# main_v2_0.net
KiCad netlist of a schematic drawn in EAGLE
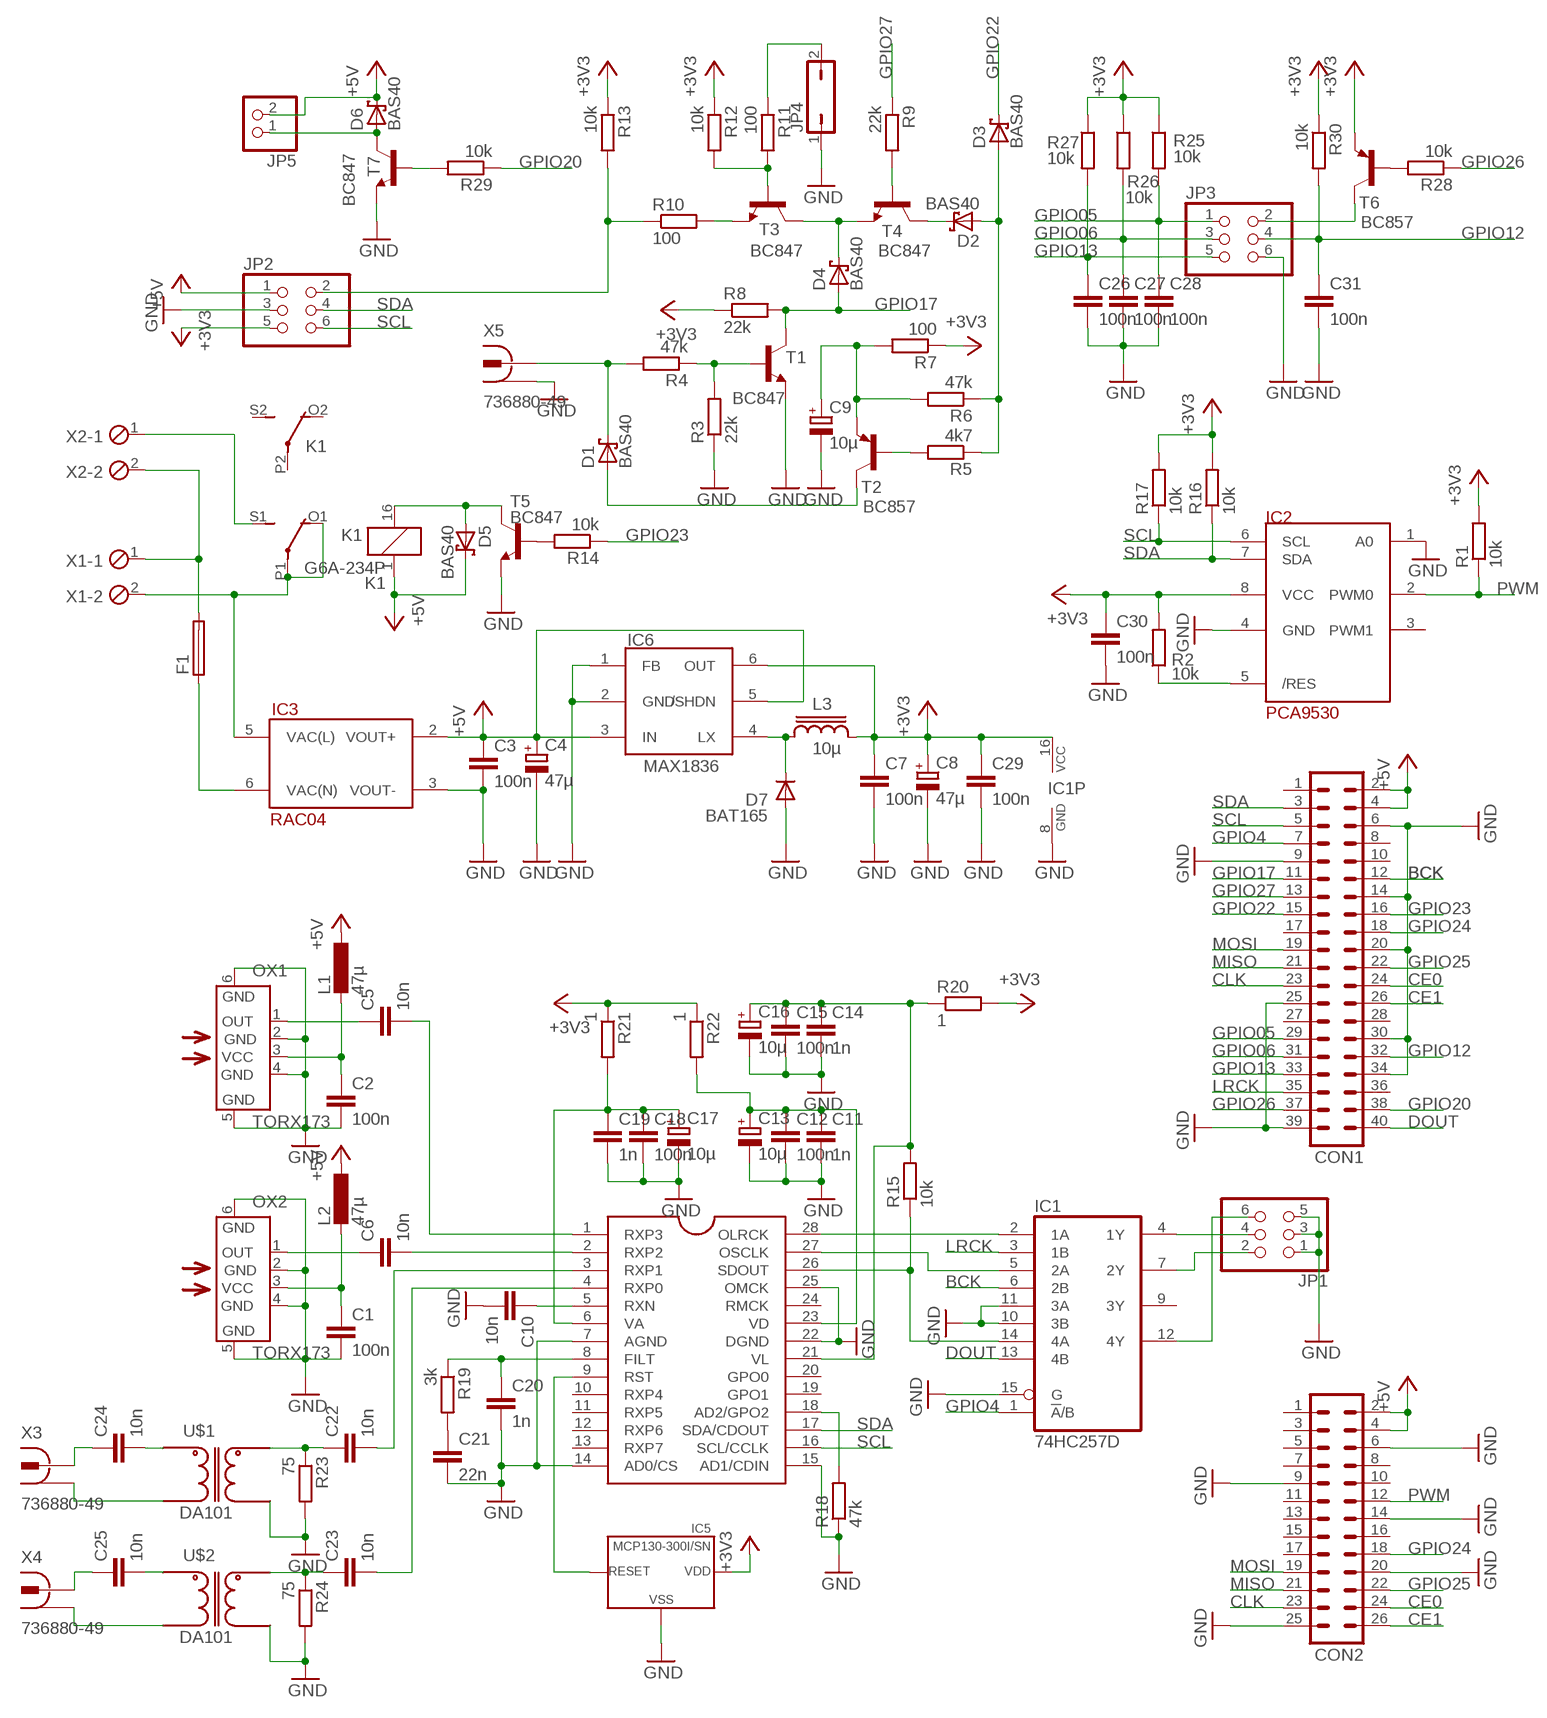
[diagram p0: schematic, sheet 1]

(export (version "E")
  (design (tool "Eeschema 10.0.6"))
  (components
    (comp (ref "C1")
      (value "100n")
      (footprint "eagle-import:C0805")
      (libsource (lib "eagle-import") (part "C-EUC0805"))
    )
    (comp (ref "C2")
      (value "100n")
      (footprint "eagle-import:C0805")
      (libsource (lib "eagle-import") (part "C-EUC0805"))
    )
    (comp (ref "C3")
      (value "100n")
      (footprint "eagle-import:C0805")
      (libsource (lib "eagle-import") (part "C-EUC0805"))
    )
    (comp (ref "C4")
      (value "47µ")
      (footprint "eagle-import:CT3528")
      (libsource (lib "eagle-import") (part "CPOL-EUCT3528"))
    )
    (comp (ref "C5")
      (value "10n")
      (footprint "eagle-import:C0805")
      (libsource (lib "eagle-import") (part "C-EUC0805"))
    )
    (comp (ref "C6")
      (value "10n")
      (footprint "eagle-import:C0805")
      (libsource (lib "eagle-import") (part "C-EUC0805"))
    )
    (comp (ref "C7")
      (value "100n")
      (footprint "eagle-import:C0805")
      (libsource (lib "eagle-import") (part "C-EUC0805"))
    )
    (comp (ref "C8")
      (value "47µ")
      (footprint "eagle-import:CT3528")
      (libsource (lib "eagle-import") (part "CPOL-EUCT3528"))
    )
    (comp (ref "C9")
      (value "10µ")
      (footprint "eagle-import:CT3216")
      (libsource (lib "eagle-import") (part "CPOL-EUCT3216"))
    )
    (comp (ref "C10")
      (value "10n")
      (footprint "eagle-import:C0805")
      (libsource (lib "eagle-import") (part "C-EUC0805"))
    )
    (comp (ref "C11")
      (value "1n")
      (footprint "eagle-import:C0805")
      (libsource (lib "eagle-import") (part "C-EUC0805"))
    )
    (comp (ref "C12")
      (value "100n")
      (footprint "eagle-import:C0805")
      (libsource (lib "eagle-import") (part "C-EUC0805"))
    )
    (comp (ref "C13")
      (value "10µ")
      (footprint "eagle-import:CT3216")
      (libsource (lib "eagle-import") (part "CPOL-EUCT3216"))
    )
    (comp (ref "C14")
      (value "1n")
      (footprint "eagle-import:C0805")
      (libsource (lib "eagle-import") (part "C-EUC0805"))
    )
    (comp (ref "C15")
      (value "100n")
      (footprint "eagle-import:C0805")
      (libsource (lib "eagle-import") (part "C-EUC0805"))
    )
    (comp (ref "C16")
      (value "10µ")
      (footprint "eagle-import:CT3216")
      (libsource (lib "eagle-import") (part "CPOL-EUCT3216"))
    )
    (comp (ref "C17")
      (value "10µ")
      (footprint "eagle-import:CT3216")
      (libsource (lib "eagle-import") (part "CPOL-EUCT3216"))
    )
    (comp (ref "C18")
      (value "100n")
      (footprint "eagle-import:C0805")
      (libsource (lib "eagle-import") (part "C-EUC0805"))
    )
    (comp (ref "C19")
      (value "1n")
      (footprint "eagle-import:C0805")
      (libsource (lib "eagle-import") (part "C-EUC0805"))
    )
    (comp (ref "C20")
      (value "1n")
      (footprint "eagle-import:C0805")
      (libsource (lib "eagle-import") (part "C-EUC0805"))
    )
    (comp (ref "C21")
      (value "22n")
      (footprint "eagle-import:C0805")
      (libsource (lib "eagle-import") (part "C-EUC0805"))
    )
    (comp (ref "C22")
      (value "10n")
      (footprint "eagle-import:C0805")
      (libsource (lib "eagle-import") (part "C-EUC0805"))
    )
    (comp (ref "C23")
      (value "10n")
      (footprint "eagle-import:C0805")
      (libsource (lib "eagle-import") (part "C-EUC0805"))
    )
    (comp (ref "C24")
      (value "10n")
      (footprint "eagle-import:C0805")
      (libsource (lib "eagle-import") (part "C-EUC0805"))
    )
    (comp (ref "C25")
      (value "10n")
      (footprint "eagle-import:C0805")
      (libsource (lib "eagle-import") (part "C-EUC0805"))
    )
    (comp (ref "C26")
      (value "100n")
      (footprint "eagle-import:C0805")
      (libsource (lib "eagle-import") (part "C-EUC0805"))
    )
    (comp (ref "C27")
      (value "100n")
      (footprint "eagle-import:C0805")
      (libsource (lib "eagle-import") (part "C-EUC0805"))
    )
    (comp (ref "C28")
      (value "100n")
      (footprint "eagle-import:C0805")
      (libsource (lib "eagle-import") (part "C-EUC0805"))
    )
    (comp (ref "C29")
      (value "100n")
      (footprint "eagle-import:C0805")
      (libsource (lib "eagle-import") (part "C-EUC0805"))
    )
    (comp (ref "C30")
      (value "100n")
      (footprint "eagle-import:C0805")
      (libsource (lib "eagle-import") (part "C-EUC0805"))
    )
    (comp (ref "C31")
      (value "100n")
      (footprint "eagle-import:C0805")
      (libsource (lib "eagle-import") (part "C-EUC0805"))
    )
    (comp (ref "CON1")
      (value "MA20-2")
      (footprint "eagle-import:MA20-2")
      (libsource (lib "eagle-import") (part "MA20-2"))
    )
    (comp (ref "CON2")
      (value "MA13-2")
      (footprint "eagle-import:MA13-2")
      (libsource (lib "eagle-import") (part "MA13-2"))
    )
    (comp (ref "D1")
      (value "BAS40")
      (footprint "eagle-import:SOT23")
      (libsource (lib "eagle-import") (part "BAS40"))
    )
    (comp (ref "D2")
      (value "BAS40")
      (footprint "eagle-import:SOT23")
      (libsource (lib "eagle-import") (part "BAS40"))
    )
    (comp (ref "D3")
      (value "BAS40")
      (footprint "eagle-import:SOT23")
      (libsource (lib "eagle-import") (part "BAS40"))
    )
    (comp (ref "D4")
      (value "BAS40")
      (footprint "eagle-import:SOT23")
      (libsource (lib "eagle-import") (part "BAS40"))
    )
    (comp (ref "D5")
      (value "BAS40")
      (footprint "eagle-import:SOT23")
      (libsource (lib "eagle-import") (part "BAS40"))
    )
    (comp (ref "D6")
      (value "BAS40")
      (footprint "eagle-import:SOT23")
      (libsource (lib "eagle-import") (part "BAS40"))
    )
    (comp (ref "D7")
      (value "BAT165")
      (footprint "eagle-import:SOD-323F")
      (libsource (lib "eagle-import") (part "DIODE-SOD-323"))
    )
    (comp (ref "F1")
      (value "19560")
      (footprint "eagle-import:19560")
      (fields (field (name "MPN") "56000001009"))
      (libsource (lib "eagle-import") (part "19560"))
    )
    (comp (ref "IC1")
      (value "74HC257D")
      (footprint "eagle-import:SO16")
      (libsource (lib "eagle-import") (part "74257DHC"))
    )
    (comp (ref "IC2")
      (value "PCA9530")
      (footprint "eagle-import:SOIC-8")
      (libsource (lib "eagle-import") (part "PCA9530"))
    )
    (comp (ref "IC3")
      (value "RAC04")
      (footprint "eagle-import:RECOM-RAC04")
      (libsource (lib "eagle-import") (part "RAC04"))
    )
    (comp (ref "IC4")
      (value "CS8416")
      (footprint "eagle-import:SO28L")
      (libsource (lib "eagle-import") (part "CS8416-SOFTWAREMODESOFTWAREMODE"))
    )
    (comp (ref "IC5")
      (value "MCP130-300I/SN")
      (footprint "eagle-import:SOT-23")
      (libsource (lib "eagle-import") (part "MCP130/SN-300I"))
    )
    (comp (ref "IC6")
      (value "MAX1836")
      (footprint "eagle-import:SOT23-6L")
      (libsource (lib "eagle-import") (part "MAX1836SOT23"))
    )
    (comp (ref "JP1")
      (value "PINHD-2X3")
      (footprint "eagle-import:2X03")
      (libsource (lib "eagle-import") (part "PINHD-2X3"))
    )
    (comp (ref "JP2")
      (value "PINHD-2X3")
      (footprint "eagle-import:2X03")
      (libsource (lib "eagle-import") (part "PINHD-2X3"))
    )
    (comp (ref "JP3")
      (value "PINHD-2X3")
      (footprint "eagle-import:2X03")
      (libsource (lib "eagle-import") (part "PINHD-2X3"))
    )
    (comp (ref "JP4")
      (value "JP1Q")
      (footprint "eagle-import:JP1")
      (libsource (lib "eagle-import") (part "JP1Q"))
    )
    (comp (ref "JP5")
      (value "PINHD-1X2")
      (footprint "eagle-import:1X02")
      (libsource (lib "eagle-import") (part "PINHD-1X2"))
    )
    (comp (ref "K1")
      (value "G6A-234P")
      (footprint "eagle-import:G6A-234P")
      (libsource (lib "eagle-import") (part "G6A-234P"))
    )
    (comp (ref "L1")
      (value "47µ")
      (footprint "eagle-import:C1210")
      (libsource (lib "eagle-import") (part "L-EU"))
    )
    (comp (ref "L2")
      (value "47µ")
      (footprint "eagle-import:C1210")
      (libsource (lib "eagle-import") (part "L-EU"))
    )
    (comp (ref "L3")
      (value "10µ")
      (footprint "eagle-import:LPS4018")
      (libsource (lib "eagle-import") (part "LPS4018"))
    )
    (comp (ref "OX1")
      (value "TORX173")
      (footprint "eagle-import:TORX173")
      (libsource (lib "eagle-import") (part "TORX173"))
    )
    (comp (ref "OX2")
      (value "TORX173")
      (footprint "eagle-import:TORX173")
      (libsource (lib "eagle-import") (part "TORX173"))
    )
    (comp (ref "R1")
      (value "10k")
      (footprint "eagle-import:R0805")
      (libsource (lib "eagle-import") (part "R-EU_R0805"))
    )
    (comp (ref "R2")
      (value "10k")
      (footprint "eagle-import:R0805")
      (libsource (lib "eagle-import") (part "R-EU_R0805"))
    )
    (comp (ref "R3")
      (value "22k")
      (footprint "eagle-import:R0805")
      (libsource (lib "eagle-import") (part "R-EU_R0805"))
    )
    (comp (ref "R4")
      (value "47k")
      (footprint "eagle-import:R0805")
      (libsource (lib "eagle-import") (part "R-EU_R0805"))
    )
    (comp (ref "R5")
      (value "4k7")
      (footprint "eagle-import:R0805")
      (libsource (lib "eagle-import") (part "R-EU_R0805"))
    )
    (comp (ref "R6")
      (value "47k")
      (footprint "eagle-import:R0805")
      (libsource (lib "eagle-import") (part "R-EU_R0805"))
    )
    (comp (ref "R7")
      (value "100")
      (footprint "eagle-import:R0805")
      (libsource (lib "eagle-import") (part "R-EU_R0805"))
    )
    (comp (ref "R8")
      (value "22k")
      (footprint "eagle-import:R0805")
      (libsource (lib "eagle-import") (part "R-EU_R0805"))
    )
    (comp (ref "R9")
      (value "22k")
      (footprint "eagle-import:R0805")
      (libsource (lib "eagle-import") (part "R-EU_R0805"))
    )
    (comp (ref "R10")
      (value "100")
      (footprint "eagle-import:R0805")
      (libsource (lib "eagle-import") (part "R-EU_R0805"))
    )
    (comp (ref "R11")
      (value "100")
      (footprint "eagle-import:R0805")
      (libsource (lib "eagle-import") (part "R-EU_R0805"))
    )
    (comp (ref "R12")
      (value "10k")
      (footprint "eagle-import:R0805")
      (libsource (lib "eagle-import") (part "R-EU_R0805"))
    )
    (comp (ref "R13")
      (value "10k")
      (footprint "eagle-import:R0805")
      (libsource (lib "eagle-import") (part "R-EU_R0805"))
    )
    (comp (ref "R14")
      (value "10k")
      (footprint "eagle-import:R0805")
      (libsource (lib "eagle-import") (part "R-EU_R0805"))
    )
    (comp (ref "R15")
      (value "10k")
      (footprint "eagle-import:R0805")
      (libsource (lib "eagle-import") (part "R-EU_R0805"))
    )
    (comp (ref "R16")
      (value "10k")
      (footprint "eagle-import:R0805")
      (libsource (lib "eagle-import") (part "R-EU_R0805"))
    )
    (comp (ref "R17")
      (value "10k")
      (footprint "eagle-import:R0805")
      (libsource (lib "eagle-import") (part "R-EU_R0805"))
    )
    (comp (ref "R18")
      (value "47k")
      (footprint "eagle-import:R0805")
      (libsource (lib "eagle-import") (part "R-EU_R0805"))
    )
    (comp (ref "R19")
      (value "3k")
      (footprint "eagle-import:R0805")
      (libsource (lib "eagle-import") (part "R-EU_R0805"))
    )
    (comp (ref "R20")
      (value "1")
      (footprint "eagle-import:R0805")
      (libsource (lib "eagle-import") (part "R-EU_R0805"))
    )
    (comp (ref "R21")
      (value "1")
      (footprint "eagle-import:R0805")
      (libsource (lib "eagle-import") (part "R-EU_R0805"))
    )
    (comp (ref "R22")
      (value "1")
      (footprint "eagle-import:R0805")
      (libsource (lib "eagle-import") (part "R-EU_R0805"))
    )
    (comp (ref "R23")
      (value "75")
      (footprint "eagle-import:R0805")
      (libsource (lib "eagle-import") (part "R-EU_R0805"))
    )
    (comp (ref "R24")
      (value "75")
      (footprint "eagle-import:R0805")
      (libsource (lib "eagle-import") (part "R-EU_R0805"))
    )
    (comp (ref "R25")
      (value "10k")
      (footprint "eagle-import:R0805")
      (libsource (lib "eagle-import") (part "R-EU_R0805"))
    )
    (comp (ref "R26")
      (value "10k")
      (footprint "eagle-import:R0805")
      (libsource (lib "eagle-import") (part "R-EU_R0805"))
    )
    (comp (ref "R27")
      (value "10k")
      (footprint "eagle-import:R0805")
      (libsource (lib "eagle-import") (part "R-EU_R0805"))
    )
    (comp (ref "R28")
      (value "10k")
      (footprint "eagle-import:R0805")
      (libsource (lib "eagle-import") (part "R-EU_R0805"))
    )
    (comp (ref "R29")
      (value "10k")
      (footprint "eagle-import:R0805")
      (libsource (lib "eagle-import") (part "R-EU_R0805"))
    )
    (comp (ref "R30")
      (value "10k")
      (footprint "eagle-import:R0805")
      (libsource (lib "eagle-import") (part "R-EU_R0805"))
    )
    (comp (ref "T1")
      (value "BC847")
      (footprint "eagle-import:SOT23-BEC")
      (libsource (lib "eagle-import") (part "-NPN-SOT23-BECBC847"))
    )
    (comp (ref "T2")
      (value "BC857")
      (footprint "eagle-import:SOT23-BEC")
      (libsource (lib "eagle-import") (part "-PNP-SOT23-BECBC857A"))
    )
    (comp (ref "T3")
      (value "BC847")
      (footprint "eagle-import:SOT23-BEC")
      (libsource (lib "eagle-import") (part "-NPN-SOT23-BECBC847"))
    )
    (comp (ref "T4")
      (value "BC847")
      (footprint "eagle-import:SOT23-BEC")
      (libsource (lib "eagle-import") (part "-NPN-SOT23-BECBC847"))
    )
    (comp (ref "T5")
      (value "BC847")
      (footprint "eagle-import:SOT23-BEC")
      (libsource (lib "eagle-import") (part "-NPN-SOT23-BECBC847"))
    )
    (comp (ref "T6")
      (value "BC857")
      (footprint "eagle-import:SOT23-BEC")
      (libsource (lib "eagle-import") (part "-PNP-SOT23-BECBC857A"))
    )
    (comp (ref "T7")
      (value "BC847")
      (footprint "eagle-import:SOT23-BEC")
      (libsource (lib "eagle-import") (part "-NPN-SOT23-BECBC847"))
    )
    (comp (ref "U$1")
      (value "DA101")
      (footprint "eagle-import:6PIN-DIL")
      (libsource (lib "eagle-import") (part "DA101"))
    )
    (comp (ref "U$2")
      (value "DA101")
      (footprint "eagle-import:6PIN-DIL")
      (libsource (lib "eagle-import") (part "DA101"))
    )
    (comp (ref "X1")
      (value "2POL500")
      (footprint "eagle-import:2POL500")
      (libsource (lib "eagle-import") (part "2POL500"))
    )
    (comp (ref "X2")
      (value "2POL500")
      (footprint "eagle-import:2POL500")
      (libsource (lib "eagle-import") (part "2POL500"))
    )
    (comp (ref "X3")
      (value "736880-49")
      (footprint "eagle-import:736880-49")
      (libsource (lib "eagle-import") (part "736880-49"))
    )
    (comp (ref "X4")
      (value "736880-49")
      (footprint "eagle-import:736880-49")
      (libsource (lib "eagle-import") (part "736880-49"))
    )
    (comp (ref "X5")
      (value "736880-49")
      (footprint "eagle-import:736880-49")
      (libsource (lib "eagle-import") (part "736880-49"))
    )
  )
  (nets
    (net (code "1") (name "+3V3") (class "Default")
      (node (ref "C29") (pin "1") (pinfunction "1_1") (pintype "passive"))
      (node (ref "C30") (pin "1") (pinfunction "1_1") (pintype "passive"))
      (node (ref "C7") (pin "1") (pinfunction "1_1") (pintype "passive"))
      (node (ref "C8") (pin "+") (pinfunction "+_+") (pintype "passive"))
      (node (ref "IC1") (pin "16") (pinfunction "VCC_16") (pintype "power_in"))
      (node (ref "IC2") (pin "8") (pinfunction "VCC_8") (pintype "power_in"))
      (node (ref "IC5") (pin "2") (pinfunction "VDD_2") (pintype "power_in"))
      (node (ref "IC6") (pin "6") (pinfunction "OUT_6") (pintype "output"))
      (node (ref "JP2") (pin "5") (pinfunction "5_5") (pintype "passive"))
      (node (ref "L3") (pin "2") (pinfunction "2_2") (pintype "passive"))
      (node (ref "R1") (pin "2") (pinfunction "2_2") (pintype "passive"))
      (node (ref "R12") (pin "1") (pinfunction "1_1") (pintype "passive"))
      (node (ref "R13") (pin "1") (pinfunction "1_1") (pintype "passive"))
      (node (ref "R16") (pin "2") (pinfunction "2_2") (pintype "passive"))
      (node (ref "R17") (pin "2") (pinfunction "2_2") (pintype "passive"))
      (node (ref "R2") (pin "2") (pinfunction "2_2") (pintype "passive"))
      (node (ref "R20") (pin "2") (pinfunction "2_2") (pintype "passive"))
      (node (ref "R21") (pin "1") (pinfunction "1_1") (pintype "passive"))
      (node (ref "R22") (pin "1") (pinfunction "1_1") (pintype "passive"))
      (node (ref "R25") (pin "1") (pinfunction "1_1") (pintype "passive"))
      (node (ref "R26") (pin "1") (pinfunction "1_1") (pintype "passive"))
      (node (ref "R27") (pin "1") (pinfunction "1_1") (pintype "passive"))
      (node (ref "R30") (pin "1") (pinfunction "1_1") (pintype "passive"))
      (node (ref "R7") (pin "1") (pinfunction "1_1") (pintype "passive"))
      (node (ref "R8") (pin "1") (pinfunction "1_1") (pintype "passive"))
      (node (ref "T6") (pin "E") (pinfunction "E_E") (pintype "passive"))
    )
    (net (code "2") (name "+5V") (class "Default")
      (node (ref "C3") (pin "1") (pinfunction "1_1") (pintype "passive"))
      (node (ref "C4") (pin "+") (pinfunction "+_+") (pintype "passive"))
      (node (ref "CON1") (pin "2") (pinfunction "2_2") (pintype "passive"))
      (node (ref "CON1") (pin "4") (pinfunction "4_4") (pintype "passive"))
      (node (ref "CON2") (pin "2") (pinfunction "2_2") (pintype "passive"))
      (node (ref "CON2") (pin "4") (pinfunction "4_4") (pintype "passive"))
      (node (ref "D5") (pin "3") (pinfunction "C_3") (pintype "passive"))
      (node (ref "D6") (pin "3") (pinfunction "C_3") (pintype "passive"))
      (node (ref "IC3") (pin "2") (pinfunction "VOUT+_2") (pintype "power_in"))
      (node (ref "IC6") (pin "3") (pinfunction "IN_3") (pintype "input"))
      (node (ref "IC6") (pin "5") (pinfunction "/SHDN_5") (pintype "input"))
      (node (ref "JP2") (pin "1") (pinfunction "1_1") (pintype "passive"))
      (node (ref "JP5") (pin "2") (pinfunction "2_2") (pintype "passive"))
      (node (ref "K1") (pin "1") (pinfunction "1_1") (pintype "passive"))
      (node (ref "L1") (pin "1") (pinfunction "1_1") (pintype "passive"))
      (node (ref "L2") (pin "1") (pinfunction "1_1") (pintype "passive"))
    )
    (net (code "3") (name "/BCK") (class "Default")
      (node (ref "CON1") (pin "12") (pinfunction "12_12") (pintype "passive"))
      (node (ref "IC1") (pin "6") (pinfunction "2B_6") (pintype "input"))
    )
    (net (code "4") (name "/CE0") (class "Default")
      (node (ref "CON1") (pin "24") (pinfunction "24_24") (pintype "passive"))
      (node (ref "CON2") (pin "24") (pinfunction "24_24") (pintype "passive"))
    )
    (net (code "5") (name "/CE1") (class "Default")
      (node (ref "CON1") (pin "26") (pinfunction "26_26") (pintype "passive"))
      (node (ref "CON2") (pin "26") (pinfunction "26_26") (pintype "passive"))
    )
    (net (code "6") (name "/CLK") (class "Default")
      (node (ref "CON1") (pin "23") (pinfunction "23_23") (pintype "passive"))
      (node (ref "CON2") (pin "23") (pinfunction "23_23") (pintype "passive"))
    )
    (net (code "7") (name "/DOUT") (class "Default")
      (node (ref "CON1") (pin "40") (pinfunction "40_40") (pintype "passive"))
      (node (ref "IC1") (pin "13") (pinfunction "4B_13") (pintype "input"))
    )
    (net (code "8") (name "/GPIO4") (class "Default")
      (node (ref "CON1") (pin "7") (pinfunction "7_7") (pintype "passive"))
      (node (ref "IC1") (pin "1") (pinfunction "~{A}/B_1") (pintype "input"))
    )
    (net (code "9") (name "/GPIO05") (class "Default")
      (node (ref "C28") (pin "1") (pinfunction "1_1") (pintype "passive"))
      (node (ref "CON1") (pin "29") (pinfunction "29_29") (pintype "passive"))
      (node (ref "JP3") (pin "1") (pinfunction "1_1") (pintype "passive"))
      (node (ref "R25") (pin "2") (pinfunction "2_2") (pintype "passive"))
    )
    (net (code "10") (name "/GPIO06") (class "Default")
      (node (ref "C27") (pin "1") (pinfunction "1_1") (pintype "passive"))
      (node (ref "CON1") (pin "31") (pinfunction "31_31") (pintype "passive"))
      (node (ref "JP3") (pin "3") (pinfunction "3_3") (pintype "passive"))
      (node (ref "R26") (pin "2") (pinfunction "2_2") (pintype "passive"))
    )
    (net (code "11") (name "/GPIO12") (class "Default")
      (node (ref "C31") (pin "1") (pinfunction "1_1") (pintype "passive"))
      (node (ref "CON1") (pin "32") (pinfunction "32_32") (pintype "passive"))
      (node (ref "JP3") (pin "4") (pinfunction "4_4") (pintype "passive"))
      (node (ref "R30") (pin "2") (pinfunction "2_2") (pintype "passive"))
    )
    (net (code "12") (name "/GPIO13") (class "Default")
      (node (ref "C26") (pin "1") (pinfunction "1_1") (pintype "passive"))
      (node (ref "CON1") (pin "33") (pinfunction "33_33") (pintype "passive"))
      (node (ref "JP3") (pin "5") (pinfunction "5_5") (pintype "passive"))
      (node (ref "R27") (pin "2") (pinfunction "2_2") (pintype "passive"))
    )
    (net (code "13") (name "/GPIO17") (class "Default")
      (node (ref "CON1") (pin "11") (pinfunction "11_11") (pintype "passive"))
      (node (ref "D4") (pin "1") (pinfunction "A_1") (pintype "passive"))
      (node (ref "R8") (pin "2") (pinfunction "2_2") (pintype "passive"))
      (node (ref "T1") (pin "C") (pinfunction "C_C") (pintype "passive"))
    )
    (net (code "14") (name "/GPIO20") (class "Default")
      (node (ref "CON1") (pin "38") (pinfunction "38_38") (pintype "passive"))
      (node (ref "R29") (pin "1") (pinfunction "1_1") (pintype "passive"))
    )
    (net (code "15") (name "/GPIO22") (class "Default")
      (node (ref "CON1") (pin "15") (pinfunction "15_15") (pintype "passive"))
      (node (ref "D3") (pin "3") (pinfunction "C_3") (pintype "passive"))
    )
    (net (code "16") (name "/GPIO23") (class "Default")
      (node (ref "CON1") (pin "16") (pinfunction "16_16") (pintype "passive"))
      (node (ref "R14") (pin "1") (pinfunction "1_1") (pintype "passive"))
    )
    (net (code "17") (name "/GPIO24") (class "Default")
      (node (ref "CON1") (pin "18") (pinfunction "18_18") (pintype "passive"))
      (node (ref "CON2") (pin "18") (pinfunction "18_18") (pintype "passive"))
    )
    (net (code "18") (name "/GPIO25") (class "Default")
      (node (ref "CON1") (pin "22") (pinfunction "22_22") (pintype "passive"))
      (node (ref "CON2") (pin "22") (pinfunction "22_22") (pintype "passive"))
    )
    (net (code "19") (name "/GPIO26") (class "Default")
      (node (ref "CON1") (pin "37") (pinfunction "37_37") (pintype "passive"))
      (node (ref "R28") (pin "1") (pinfunction "1_1") (pintype "passive"))
    )
    (net (code "20") (name "/GPIO27") (class "Default")
      (node (ref "CON1") (pin "13") (pinfunction "13_13") (pintype "passive"))
      (node (ref "R9") (pin "1") (pinfunction "1_1") (pintype "passive"))
    )
    (net (code "21") (name "/LRCK") (class "Default")
      (node (ref "CON1") (pin "35") (pinfunction "35_35") (pintype "passive"))
      (node (ref "IC1") (pin "3") (pinfunction "1B_3") (pintype "input"))
    )
    (net (code "22") (name "/MISO") (class "Default")
      (node (ref "CON1") (pin "21") (pinfunction "21_21") (pintype "passive"))
      (node (ref "CON2") (pin "21") (pinfunction "21_21") (pintype "passive"))
    )
    (net (code "23") (name "/MOSI") (class "Default")
      (node (ref "CON1") (pin "19") (pinfunction "19_19") (pintype "passive"))
      (node (ref "CON2") (pin "19") (pinfunction "19_19") (pintype "passive"))
    )
    (net (code "24") (name "/PWM") (class "Default")
      (node (ref "CON2") (pin "12") (pinfunction "12_12") (pintype "passive"))
      (node (ref "IC2") (pin "2") (pinfunction "PWM0_2") (pintype "output"))
      (node (ref "R1") (pin "1") (pinfunction "1_1") (pintype "passive"))
    )
    (net (code "25") (name "/SCL") (class "Default")
      (node (ref "CON1") (pin "5") (pinfunction "5_5") (pintype "passive"))
      (node (ref "IC2") (pin "6") (pinfunction "SCL_6") (pintype "input"))
      (node (ref "IC4") (pin "16") (pinfunction "SCL/CCLK_16") (pintype "bidirectional"))
      (node (ref "JP2") (pin "6") (pinfunction "6_6") (pintype "passive"))
      (node (ref "R17") (pin "1") (pinfunction "1_1") (pintype "passive"))
    )
    (net (code "26") (name "/SDA") (class "Default")
      (node (ref "CON1") (pin "3") (pinfunction "3_3") (pintype "passive"))
      (node (ref "IC2") (pin "7") (pinfunction "SDA_7") (pintype "input"))
      (node (ref "IC4") (pin "17") (pinfunction "SDA/CDOUT_17") (pintype "bidirectional"))
      (node (ref "JP2") (pin "4") (pinfunction "4_4") (pintype "passive"))
      (node (ref "R16") (pin "1") (pinfunction "1_1") (pintype "passive"))
    )
    (net (code "27") (name "GND") (class "Default")
      (node (ref "C1") (pin "2") (pinfunction "2_2") (pintype "passive"))
      (node (ref "C10") (pin "2") (pinfunction "2_2") (pintype "passive"))
      (node (ref "C11") (pin "2") (pinfunction "2_2") (pintype "passive"))
      (node (ref "C12") (pin "2") (pinfunction "2_2") (pintype "passive"))
      (node (ref "C13") (pin "-") (pinfunction "-_-") (pintype "passive"))
      (node (ref "C14") (pin "2") (pinfunction "2_2") (pintype "passive"))
      (node (ref "C15") (pin "2") (pinfunction "2_2") (pintype "passive"))
      (node (ref "C16") (pin "-") (pinfunction "-_-") (pintype "passive"))
      (node (ref "C17") (pin "-") (pinfunction "-_-") (pintype "passive"))
      (node (ref "C18") (pin "2") (pinfunction "2_2") (pintype "passive"))
      (node (ref "C19") (pin "2") (pinfunction "2_2") (pintype "passive"))
      (node (ref "C2") (pin "2") (pinfunction "2_2") (pintype "passive"))
      (node (ref "C20") (pin "2") (pinfunction "2_2") (pintype "passive"))
      (node (ref "C21") (pin "2") (pinfunction "2_2") (pintype "passive"))
      (node (ref "C26") (pin "2") (pinfunction "2_2") (pintype "passive"))
      (node (ref "C27") (pin "2") (pinfunction "2_2") (pintype "passive"))
      (node (ref "C28") (pin "2") (pinfunction "2_2") (pintype "passive"))
      (node (ref "C29") (pin "2") (pinfunction "2_2") (pintype "passive"))
      (node (ref "C3") (pin "2") (pinfunction "2_2") (pintype "passive"))
      (node (ref "C30") (pin "2") (pinfunction "2_2") (pintype "passive"))
      (node (ref "C31") (pin "2") (pinfunction "2_2") (pintype "passive"))
      (node (ref "C4") (pin "-") (pinfunction "-_-") (pintype "passive"))
      (node (ref "C7") (pin "2") (pinfunction "2_2") (pintype "passive"))
      (node (ref "C8") (pin "-") (pinfunction "-_-") (pintype "passive"))
      (node (ref "C9") (pin "-") (pinfunction "-_-") (pintype "passive"))
      (node (ref "CON1") (pin "14") (pinfunction "14_14") (pintype "passive"))
      (node (ref "CON1") (pin "20") (pinfunction "20_20") (pintype "passive"))
      (node (ref "CON1") (pin "25") (pinfunction "25_25") (pintype "passive"))
      (node (ref "CON1") (pin "30") (pinfunction "30_30") (pintype "passive"))
      (node (ref "CON1") (pin "34") (pinfunction "34_34") (pintype "passive"))
      (node (ref "CON1") (pin "39") (pinfunction "39_39") (pintype "passive"))
      (node (ref "CON1") (pin "6") (pinfunction "6_6") (pintype "passive"))
      (node (ref "CON1") (pin "9") (pinfunction "9_9") (pintype "passive"))
      (node (ref "CON2") (pin "14") (pinfunction "14_14") (pintype "passive"))
      (node (ref "CON2") (pin "20") (pinfunction "20_20") (pintype "passive"))
      (node (ref "CON2") (pin "25") (pinfunction "25_25") (pintype "passive"))
      (node (ref "CON2") (pin "6") (pinfunction "6_6") (pintype "passive"))
      (node (ref "CON2") (pin "9") (pinfunction "9_9") (pintype "passive"))
      (node (ref "D7") (pin "A") (pinfunction "A_A") (pintype "passive"))
      (node (ref "IC1") (pin "10") (pinfunction "3B_10") (pintype "input"))
      (node (ref "IC1") (pin "11") (pinfunction "3A_11") (pintype "input"))
      (node (ref "IC1") (pin "15") (pinfunction "G_15") (pintype "input"))
      (node (ref "IC1") (pin "8") (pinfunction "GND_8") (pintype "power_in"))
      (node (ref "IC2") (pin "1") (pinfunction "A0_1") (pintype "input"))
      (node (ref "IC2") (pin "4") (pinfunction "GND_4") (pintype "power_in"))
      (node (ref "IC3") (pin "3") (pinfunction "VOUT-_3") (pintype "power_in"))
      (node (ref "IC4") (pin "14") (pinfunction "AD0/CS_14") (pintype "bidirectional"))
      (node (ref "IC4") (pin "15") (pinfunction "AD1/CDIN_15") (pintype "bidirectional"))
      (node (ref "IC4") (pin "22") (pinfunction "DGND_22") (pintype "bidirectional"))
      (node (ref "IC4") (pin "25") (pinfunction "OMCK_25") (pintype "bidirectional"))
      (node (ref "IC4") (pin "7") (pinfunction "AGND_7") (pintype "bidirectional"))
      (node (ref "IC5") (pin "3") (pinfunction "VSS_3") (pintype "power_in"))
      (node (ref "IC6") (pin "1") (pinfunction "FB_1") (pintype "input"))
      (node (ref "IC6") (pin "2") (pinfunction "GND_2") (pintype "power_in"))
      (node (ref "JP1") (pin "1") (pinfunction "1_1") (pintype "passive"))
      (node (ref "JP1") (pin "3") (pinfunction "3_3") (pintype "passive"))
      (node (ref "JP1") (pin "5") (pinfunction "5_5") (pintype "passive"))
      (node (ref "JP2") (pin "3") (pinfunction "3_3") (pintype "passive"))
      (node (ref "JP3") (pin "6") (pinfunction "6_6") (pintype "passive"))
      (node (ref "JP4") (pin "1") (pinfunction "1_1") (pintype "passive"))
      (node (ref "OX1") (pin "2") (pinfunction "GND_2") (pintype "power_in"))
      (node (ref "OX1") (pin "4") (pinfunction "GND_4") (pintype "power_in"))
      (node (ref "OX1") (pin "5") (pinfunction "GND_5") (pintype "power_in"))
      (node (ref "OX1") (pin "6") (pinfunction "GND_6") (pintype "power_in"))
      (node (ref "OX2") (pin "2") (pinfunction "GND_2") (pintype "power_in"))
      (node (ref "OX2") (pin "4") (pinfunction "GND_4") (pintype "power_in"))
      (node (ref "OX2") (pin "5") (pinfunction "GND_5") (pintype "power_in"))
      (node (ref "OX2") (pin "6") (pinfunction "GND_6") (pintype "power_in"))
      (node (ref "R18") (pin "1") (pinfunction "1_1") (pintype "passive"))
      (node (ref "R23") (pin "2") (pinfunction "2_2") (pintype "passive"))
      (node (ref "R24") (pin "2") (pinfunction "2_2") (pintype "passive"))
      (node (ref "R3") (pin "1") (pinfunction "1_1") (pintype "passive"))
      (node (ref "T1") (pin "E") (pinfunction "E_E") (pintype "passive"))
      (node (ref "T5") (pin "E") (pinfunction "E_E") (pintype "passive"))
      (node (ref "T7") (pin "E") (pinfunction "E_E") (pintype "passive"))
      (node (ref "U$1") (pin "4") (pinfunction "4_4") (pintype "bidirectional"))
      (node (ref "U$2") (pin "4") (pinfunction "4_4") (pintype "bidirectional"))
      (node (ref "X5") (pin "1") (pinfunction "1_1") (pintype "passive"))
      (node (ref "X5") (pin "1@1") (pinfunction "1_1@1") (pintype "passive"))
      (node (ref "X5") (pin "1@2") (pinfunction "1_1@2") (pintype "passive"))
    )
    (net (code "28") (name "Net-(C9-Pad+)") (class "Default")
      (node (ref "C9") (pin "+") (pinfunction "+_+") (pintype "passive"))
      (node (ref "R6") (pin "2") (pinfunction "2_2") (pintype "passive"))
      (node (ref "R7") (pin "2") (pinfunction "2_2") (pintype "passive"))
      (node (ref "T2") (pin "E") (pinfunction "E_E") (pintype "passive"))
    )
    (net (code "29") (name "Net-(C21-Pad1)") (class "Default")
      (node (ref "C21") (pin "1") (pinfunction "1_1") (pintype "passive"))
      (node (ref "R19") (pin "2") (pinfunction "2_2") (pintype "passive"))
    )
    (net (code "30") (name "Net-(C22-Pad1)") (class "Default")
      (node (ref "C22") (pin "1") (pinfunction "1_1") (pintype "passive"))
      (node (ref "R23") (pin "1") (pinfunction "1_1") (pintype "passive"))
      (node (ref "U$1") (pin "6") (pinfunction "6_6") (pintype "bidirectional"))
    )
    (net (code "31") (name "Net-(C23-Pad1)") (class "Default")
      (node (ref "C23") (pin "1") (pinfunction "1_1") (pintype "passive"))
      (node (ref "R24") (pin "1") (pinfunction "1_1") (pintype "passive"))
      (node (ref "U$2") (pin "6") (pinfunction "6_6") (pintype "bidirectional"))
    )
    (net (code "32") (name "Net-(C24-Pad1)") (class "Default")
      (node (ref "C24") (pin "1") (pinfunction "1_1") (pintype "passive"))
      (node (ref "X3") (pin "2") (pinfunction "2_2") (pintype "passive"))
    )
    (net (code "33") (name "Net-(C24-Pad2)") (class "Default")
      (node (ref "C24") (pin "2") (pinfunction "2_2") (pintype "passive"))
      (node (ref "U$1") (pin "1") (pinfunction "1_1") (pintype "bidirectional"))
    )
    (net (code "34") (name "Net-(C25-Pad1)") (class "Default")
      (node (ref "C25") (pin "1") (pinfunction "1_1") (pintype "passive"))
      (node (ref "X4") (pin "2") (pinfunction "2_2") (pintype "passive"))
    )
    (net (code "35") (name "Net-(C25-Pad2)") (class "Default")
      (node (ref "C25") (pin "2") (pinfunction "2_2") (pintype "passive"))
      (node (ref "U$2") (pin "1") (pinfunction "1_1") (pintype "bidirectional"))
    )
    (net (code "36") (name "Net-(D1-A)") (class "Default")
      (node (ref "D1") (pin "1") (pinfunction "A_1") (pintype "passive"))
      (node (ref "T2") (pin "C") (pinfunction "C_C") (pintype "passive"))
    )
    (net (code "37") (name "Net-(D1-C)") (class "Default")
      (node (ref "D1") (pin "3") (pinfunction "C_3") (pintype "passive"))
      (node (ref "R4") (pin "2") (pinfunction "2_2") (pintype "passive"))
      (node (ref "X5") (pin "2") (pinfunction "2_2") (pintype "passive"))
    )
    (net (code "38") (name "Net-(D2-A)") (class "Default")
      (node (ref "D2") (pin "1") (pinfunction "A_1") (pintype "passive"))
      (node (ref "D3") (pin "1") (pinfunction "A_1") (pintype "passive"))
      (node (ref "R5") (pin "1") (pinfunction "1_1") (pintype "passive"))
      (node (ref "R6") (pin "1") (pinfunction "1_1") (pintype "passive"))
    )
    (net (code "39") (name "Net-(D2-C)") (class "Default")
      (node (ref "D2") (pin "3") (pinfunction "C_3") (pintype "passive"))
      (node (ref "T4") (pin "C") (pinfunction "C_C") (pintype "passive"))
    )
    (net (code "40") (name "Net-(D4-C)") (class "Default")
      (node (ref "D4") (pin "3") (pinfunction "C_3") (pintype "passive"))
      (node (ref "T3") (pin "C") (pinfunction "C_C") (pintype "passive"))
      (node (ref "T4") (pin "E") (pinfunction "E_E") (pintype "passive"))
    )
    (net (code "41") (name "Net-(D5-A)") (class "Default")
      (node (ref "D5") (pin "1") (pinfunction "A_1") (pintype "passive"))
      (node (ref "K1") (pin "16") (pinfunction "2_16") (pintype "passive"))
      (node (ref "T5") (pin "C") (pinfunction "C_C") (pintype "passive"))
    )
    (net (code "42") (name "Net-(D6-A)") (class "Default")
      (node (ref "D6") (pin "1") (pinfunction "A_1") (pintype "passive"))
      (node (ref "JP5") (pin "1") (pinfunction "1_1") (pintype "passive"))
      (node (ref "T7") (pin "C") (pinfunction "C_C") (pintype "passive"))
    )
    (net (code "43") (name "Net-(IC1A-1A)") (class "Default")
      (node (ref "IC1") (pin "2") (pinfunction "1A_2") (pintype "input"))
      (node (ref "IC4") (pin "28") (pinfunction "OLRCK_28") (pintype "bidirectional"))
    )
    (net (code "44") (name "Net-(IC1A-1Y)") (class "Default")
      (node (ref "IC1") (pin "4") (pinfunction "1Y_4") (pintype "tri_state"))
      (node (ref "JP1") (pin "4") (pinfunction "4_4") (pintype "passive"))
    )
    (net (code "45") (name "Net-(IC1A-2A)") (class "Default")
      (node (ref "IC1") (pin "5") (pinfunction "2A_5") (pintype "input"))
      (node (ref "IC4") (pin "27") (pinfunction "OSCLK_27") (pintype "bidirectional"))
    )
    (net (code "46") (name "Net-(IC1A-2Y)") (class "Default")
      (node (ref "IC1") (pin "7") (pinfunction "2Y_7") (pintype "tri_state"))
      (node (ref "JP1") (pin "2") (pinfunction "2_2") (pintype "passive"))
    )
    (net (code "47") (name "Net-(IC1A-4A)") (class "Default")
      (node (ref "IC1") (pin "14") (pinfunction "4A_14") (pintype "input"))
      (node (ref "IC4") (pin "26") (pinfunction "SDOUT_26") (pintype "bidirectional"))
      (node (ref "R15") (pin "1") (pinfunction "1_1") (pintype "passive"))
    )
    (net (code "48") (name "Net-(IC1A-4Y)") (class "Default")
      (node (ref "IC1") (pin "12") (pinfunction "4Y_12") (pintype "tri_state"))
      (node (ref "JP1") (pin "6") (pinfunction "6_6") (pintype "passive"))
    )
    (net (code "49") (name "Net-(IC2-{slash}RES)") (class "Default")
      (node (ref "IC2") (pin "5") (pinfunction "/RES_5") (pintype "input"))
      (node (ref "R2") (pin "1") (pinfunction "1_1") (pintype "passive"))
    )
    (net (code "50") (name "Net-(IC3-VAC(L))") (class "Default")
      (node (ref "IC3") (pin "5") (pinfunction "VAC(L)_5") (pintype "power_in"))
      (node (ref "K1") (pin "O1") (pinfunction "O_O1") (pintype "passive"))
      (node (ref "K1") (pin "P1") (pinfunction "P_P1") (pintype "passive"))
      (node (ref "X1") (pin "2") (pinfunction "1_2") (pintype "passive"))
    )
    (net (code "51") (name "Net-(IC3-VAC(N))") (class "Default")
      (node (ref "F1") (pin "1") (pinfunction "1_1") (pintype "passive"))
      (node (ref "IC3") (pin "6") (pinfunction "VAC(N)_6") (pintype "power_in"))
    )
    (net (code "52") (name "Net-(IC4-AD2{slash}GPO2)") (class "Default")
      (node (ref "IC4") (pin "18") (pinfunction "AD2/GPO2_18") (pintype "bidirectional"))
      (node (ref "R18") (pin "2") (pinfunction "2_2") (pintype "passive"))
    )
    (net (code "53") (name "Net-(IC4-FILT)") (class "Default")
      (node (ref "C20") (pin "1") (pinfunction "1_1") (pintype "passive"))
      (node (ref "IC4") (pin "8") (pinfunction "FILT_8") (pintype "bidirectional"))
      (node (ref "R19") (pin "1") (pinfunction "1_1") (pintype "passive"))
    )
    (net (code "54") (name "Net-(IC4-RST)") (class "Default")
      (node (ref "IC4") (pin "9") (pinfunction "RST_9") (pintype "bidirectional"))
      (node (ref "IC5") (pin "1") (pinfunction "RESET_1") (pintype "output"))
    )
    (net (code "55") (name "Net-(IC4-RXN)") (class "Default")
      (node (ref "C10") (pin "1") (pinfunction "1_1") (pintype "passive"))
      (node (ref "IC4") (pin "5") (pinfunction "RXN_5") (pintype "bidirectional"))
    )
    (net (code "56") (name "Net-(IC4-RXP0)") (class "Default")
      (node (ref "C23") (pin "2") (pinfunction "2_2") (pintype "passive"))
      (node (ref "IC4") (pin "4") (pinfunction "RXP0_4") (pintype "bidirectional"))
    )
    (net (code "57") (name "Net-(IC4-RXP1)") (class "Default")
      (node (ref "C22") (pin "2") (pinfunction "2_2") (pintype "passive"))
      (node (ref "IC4") (pin "3") (pinfunction "RXP1_3") (pintype "bidirectional"))
    )
    (net (code "58") (name "Net-(IC4-RXP2)") (class "Default")
      (node (ref "C6") (pin "2") (pinfunction "2_2") (pintype "passive"))
      (node (ref "IC4") (pin "2") (pinfunction "RXP2_2") (pintype "bidirectional"))
    )
    (net (code "59") (name "Net-(IC4-RXP3)") (class "Default")
      (node (ref "C5") (pin "2") (pinfunction "2_2") (pintype "passive"))
      (node (ref "IC4") (pin "1") (pinfunction "RXP3_1") (pintype "bidirectional"))
    )
    (net (code "60") (name "Net-(IC4-VA)") (class "Default")
      (node (ref "C17") (pin "+") (pinfunction "+_+") (pintype "passive"))
      (node (ref "C18") (pin "1") (pinfunction "1_1") (pintype "passive"))
      (node (ref "C19") (pin "1") (pinfunction "1_1") (pintype "passive"))
      (node (ref "IC4") (pin "6") (pinfunction "VA_6") (pintype "bidirectional"))
      (node (ref "R21") (pin "2") (pinfunction "2_2") (pintype "passive"))
    )
    (net (code "61") (name "Net-(IC4-VD)") (class "Default")
      (node (ref "C11") (pin "1") (pinfunction "1_1") (pintype "passive"))
      (node (ref "C12") (pin "1") (pinfunction "1_1") (pintype "passive"))
      (node (ref "C13") (pin "+") (pinfunction "+_+") (pintype "passive"))
      (node (ref "IC4") (pin "23") (pinfunction "VD_23") (pintype "bidirectional"))
      (node (ref "R22") (pin "2") (pinfunction "2_2") (pintype "passive"))
    )
    (net (code "62") (name "Net-(IC4-VL)") (class "Default")
      (node (ref "C14") (pin "1") (pinfunction "1_1") (pintype "passive"))
      (node (ref "C15") (pin "1") (pinfunction "1_1") (pintype "passive"))
      (node (ref "C16") (pin "+") (pinfunction "+_+") (pintype "passive"))
      (node (ref "IC4") (pin "21") (pinfunction "VL_21") (pintype "bidirectional"))
      (node (ref "R15") (pin "2") (pinfunction "2_2") (pintype "passive"))
      (node (ref "R20") (pin "1") (pinfunction "1_1") (pintype "passive"))
    )
    (net (code "63") (name "Net-(IC6-LX)") (class "Default")
      (node (ref "D7") (pin "C") (pinfunction "C_C") (pintype "passive"))
      (node (ref "IC6") (pin "4") (pinfunction "LX_4") (pintype "output"))
      (node (ref "L3") (pin "1") (pinfunction "1_1") (pintype "passive"))
    )
    (net (code "64") (name "Net-(JP2-Pad2)") (class "Default")
      (node (ref "JP2") (pin "2") (pinfunction "2_2") (pintype "passive"))
      (node (ref "R10") (pin "1") (pinfunction "1_1") (pintype "passive"))
      (node (ref "R13") (pin "2") (pinfunction "2_2") (pintype "passive"))
    )
    (net (code "65") (name "Net-(JP3-Pad2)") (class "Default")
      (node (ref "JP3") (pin "2") (pinfunction "2_2") (pintype "passive"))
      (node (ref "T6") (pin "C") (pinfunction "C_C") (pintype "passive"))
    )
    (net (code "66") (name "Net-(JP4-Pad2)") (class "Default")
      (node (ref "JP4") (pin "2") (pinfunction "2_2") (pintype "passive"))
      (node (ref "R11") (pin "1") (pinfunction "1_1") (pintype "passive"))
    )
    (net (code "67") (name "Net-(K1B-S)") (class "Default")
      (node (ref "K1") (pin "S1") (pinfunction "S_S1") (pintype "passive"))
      (node (ref "X2") (pin "1") (pinfunction "1_1") (pintype "passive"))
    )
    (net (code "68") (name "Net-(OX1-OUT)") (class "Default")
      (node (ref "C5") (pin "1") (pinfunction "1_1") (pintype "passive"))
      (node (ref "OX1") (pin "1") (pinfunction "OUT_1") (pintype "output"))
    )
    (net (code "69") (name "Net-(OX1-VCC)") (class "Default")
      (node (ref "C2") (pin "1") (pinfunction "1_1") (pintype "passive"))
      (node (ref "L1") (pin "2") (pinfunction "2_2") (pintype "passive"))
      (node (ref "OX1") (pin "3") (pinfunction "VCC_3") (pintype "power_in"))
    )
    (net (code "70") (name "Net-(OX2-OUT)") (class "Default")
      (node (ref "C6") (pin "1") (pinfunction "1_1") (pintype "passive"))
      (node (ref "OX2") (pin "1") (pinfunction "OUT_1") (pintype "output"))
    )
    (net (code "71") (name "Net-(OX2-VCC)") (class "Default")
      (node (ref "C1") (pin "1") (pinfunction "1_1") (pintype "passive"))
      (node (ref "L2") (pin "2") (pinfunction "2_2") (pintype "passive"))
      (node (ref "OX2") (pin "3") (pinfunction "VCC_3") (pintype "power_in"))
    )
    (net (code "72") (name "Net-(R3-Pad2)") (class "Default")
      (node (ref "R3") (pin "2") (pinfunction "2_2") (pintype "passive"))
      (node (ref "R4") (pin "1") (pinfunction "1_1") (pintype "passive"))
      (node (ref "T1") (pin "B") (pinfunction "B_B") (pintype "passive"))
    )
    (net (code "73") (name "Net-(R5-Pad2)") (class "Default")
      (node (ref "R5") (pin "2") (pinfunction "2_2") (pintype "passive"))
      (node (ref "T2") (pin "B") (pinfunction "B_B") (pintype "passive"))
    )
    (net (code "74") (name "Net-(R9-Pad2)") (class "Default")
      (node (ref "R9") (pin "2") (pinfunction "2_2") (pintype "passive"))
      (node (ref "T4") (pin "B") (pinfunction "B_B") (pintype "passive"))
    )
    (net (code "75") (name "Net-(R10-Pad2)") (class "Default")
      (node (ref "R10") (pin "2") (pinfunction "2_2") (pintype "passive"))
      (node (ref "T3") (pin "E") (pinfunction "E_E") (pintype "passive"))
    )
    (net (code "76") (name "Net-(R11-Pad2)") (class "Default")
      (node (ref "R11") (pin "2") (pinfunction "2_2") (pintype "passive"))
      (node (ref "R12") (pin "2") (pinfunction "2_2") (pintype "passive"))
      (node (ref "T3") (pin "B") (pinfunction "B_B") (pintype "passive"))
    )
    (net (code "77") (name "Net-(R14-Pad2)") (class "Default")
      (node (ref "R14") (pin "2") (pinfunction "2_2") (pintype "passive"))
      (node (ref "T5") (pin "B") (pinfunction "B_B") (pintype "passive"))
    )
    (net (code "78") (name "Net-(R28-Pad2)") (class "Default")
      (node (ref "R28") (pin "2") (pinfunction "2_2") (pintype "passive"))
      (node (ref "T6") (pin "B") (pinfunction "B_B") (pintype "passive"))
    )
    (net (code "79") (name "Net-(R29-Pad2)") (class "Default")
      (node (ref "R29") (pin "2") (pinfunction "2_2") (pintype "passive"))
      (node (ref "T7") (pin "B") (pinfunction "B_B") (pintype "passive"))
    )
    (net (code "80") (name "Net-(U$1-Pad3)") (class "Default")
      (node (ref "U$1") (pin "3") (pinfunction "3_3") (pintype "bidirectional"))
      (node (ref "X3") (pin "1") (pinfunction "1_1") (pintype "passive"))
      (node (ref "X3") (pin "1@1") (pinfunction "1_1@1") (pintype "passive"))
      (node (ref "X3") (pin "1@2") (pinfunction "1_1@2") (pintype "passive"))
    )
    (net (code "81") (name "Net-(U$2-Pad3)") (class "Default")
      (node (ref "U$2") (pin "3") (pinfunction "3_3") (pintype "bidirectional"))
      (node (ref "X4") (pin "1") (pinfunction "1_1") (pintype "passive"))
      (node (ref "X4") (pin "1@1") (pinfunction "1_1@1") (pintype "passive"))
      (node (ref "X4") (pin "1@2") (pinfunction "1_1@2") (pintype "passive"))
    )
    (net (code "82") (name "Net-(X2B-1)") (class "Default")
      (node (ref "F1") (pin "2") (pinfunction "2_2") (pintype "passive"))
      (node (ref "X1") (pin "1") (pinfunction "1_1") (pintype "passive"))
      (node (ref "X2") (pin "2") (pinfunction "1_2") (pintype "passive"))
    )
    (net (code "83") (name "unconnected-(CON1-Pad1)") (class "Default")
      (node (ref "CON1") (pin "1") (pinfunction "1_1") (pintype "passive"))
    )
    (net (code "84") (name "unconnected-(CON1-Pad8)") (class "Default")
      (node (ref "CON1") (pin "8") (pinfunction "8_8") (pintype "passive"))
    )
    (net (code "85") (name "unconnected-(CON1-Pad10)") (class "Default")
      (node (ref "CON1") (pin "10") (pinfunction "10_10") (pintype "passive"))
    )
    (net (code "86") (name "unconnected-(CON1-Pad17)") (class "Default")
      (node (ref "CON1") (pin "17") (pinfunction "17_17") (pintype "passive"))
    )
    (net (code "87") (name "unconnected-(CON1-Pad27)") (class "Default")
      (node (ref "CON1") (pin "27") (pinfunction "27_27") (pintype "passive"))
    )
    (net (code "88") (name "unconnected-(CON1-Pad28)") (class "Default")
      (node (ref "CON1") (pin "28") (pinfunction "28_28") (pintype "passive"))
    )
    (net (code "89") (name "unconnected-(CON1-Pad36)") (class "Default")
      (node (ref "CON1") (pin "36") (pinfunction "36_36") (pintype "passive"))
    )
    (net (code "90") (name "unconnected-(CON2-Pad1)") (class "Default")
      (node (ref "CON2") (pin "1") (pinfunction "1_1") (pintype "passive"))
    )
    (net (code "91") (name "unconnected-(CON2-Pad3)") (class "Default")
      (node (ref "CON2") (pin "3") (pinfunction "3_3") (pintype "passive"))
    )
    (net (code "92") (name "unconnected-(CON2-Pad5)") (class "Default")
      (node (ref "CON2") (pin "5") (pinfunction "5_5") (pintype "passive"))
    )
    (net (code "93") (name "unconnected-(CON2-Pad7)") (class "Default")
      (node (ref "CON2") (pin "7") (pinfunction "7_7") (pintype "passive"))
    )
    (net (code "94") (name "unconnected-(CON2-Pad8)") (class "Default")
      (node (ref "CON2") (pin "8") (pinfunction "8_8") (pintype "passive"))
    )
    (net (code "95") (name "unconnected-(CON2-Pad10)") (class "Default")
      (node (ref "CON2") (pin "10") (pinfunction "10_10") (pintype "passive"))
    )
    (net (code "96") (name "unconnected-(CON2-Pad11)") (class "Default")
      (node (ref "CON2") (pin "11") (pinfunction "11_11") (pintype "passive"))
    )
    (net (code "97") (name "unconnected-(CON2-Pad13)") (class "Default")
      (node (ref "CON2") (pin "13") (pinfunction "13_13") (pintype "passive"))
    )
    (net (code "98") (name "unconnected-(CON2-Pad15)") (class "Default")
      (node (ref "CON2") (pin "15") (pinfunction "15_15") (pintype "passive"))
    )
    (net (code "99") (name "unconnected-(CON2-Pad16)") (class "Default")
      (node (ref "CON2") (pin "16") (pinfunction "16_16") (pintype "passive"))
    )
    (net (code "100") (name "unconnected-(CON2-Pad17)") (class "Default")
      (node (ref "CON2") (pin "17") (pinfunction "17_17") (pintype "passive"))
    )
    (net (code "101") (name "unconnected-(IC1A-3Y-Pad9)") (class "Default")
      (node (ref "IC1") (pin "9") (pinfunction "3Y_9") (pintype "tri_state"))
    )
    (net (code "102") (name "unconnected-(IC2-PWM1-Pad3)") (class "Default")
      (node (ref "IC2") (pin "3") (pinfunction "PWM1_3") (pintype "output"))
    )
    (net (code "103") (name "unconnected-(IC4-GPO0-Pad20)") (class "Default")
      (node (ref "IC4") (pin "20") (pinfunction "GPO0_20") (pintype "bidirectional"))
    )
    (net (code "104") (name "unconnected-(IC4-GPO1-Pad19)") (class "Default")
      (node (ref "IC4") (pin "19") (pinfunction "GPO1_19") (pintype "bidirectional"))
    )
    (net (code "105") (name "unconnected-(IC4-RMCK-Pad24)") (class "Default")
      (node (ref "IC4") (pin "24") (pinfunction "RMCK_24") (pintype "bidirectional"))
    )
    (net (code "106") (name "unconnected-(IC4-RXP4-Pad10)") (class "Default")
      (node (ref "IC4") (pin "10") (pinfunction "RXP4_10") (pintype "bidirectional"))
    )
    (net (code "107") (name "unconnected-(IC4-RXP5-Pad11)") (class "Default")
      (node (ref "IC4") (pin "11") (pinfunction "RXP5_11") (pintype "bidirectional"))
    )
    (net (code "108") (name "unconnected-(IC4-RXP6-Pad12)") (class "Default")
      (node (ref "IC4") (pin "12") (pinfunction "RXP6_12") (pintype "bidirectional"))
    )
    (net (code "109") (name "unconnected-(IC4-RXP7-Pad13)") (class "Default")
      (node (ref "IC4") (pin "13") (pinfunction "RXP7_13") (pintype "bidirectional"))
    )
    (net (code "110") (name "unconnected-(K1C-O-PadO2)") (class "Default")
      (node (ref "K1") (pin "O2") (pinfunction "O_O2") (pintype "passive"))
    )
    (net (code "111") (name "unconnected-(K1C-P-PadP2)") (class "Default")
      (node (ref "K1") (pin "P2") (pinfunction "P_P2") (pintype "passive"))
    )
    (net (code "112") (name "unconnected-(K1C-S-PadS2)") (class "Default")
      (node (ref "K1") (pin "S2") (pinfunction "S_S2") (pintype "passive"))
    )
  )
)
